# converter_adapter.net
KiCad netlist of a schematic drawn in EAGLE
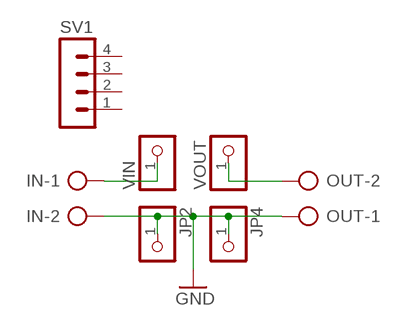
[diagram p0: schematic, sheet 1]

(export (version "E")
  (design (tool "Eeschema 10.0.6"))
  (components
    (comp (ref "IN")
      (value "AK500/2-H")
      (footprint "eagle-import:AK500_2-H")
      (libsource (lib "eagle-import") (part "AK500/2-H"))
    )
    (comp (ref "JP2")
      (value "PINHD-1X1")
      (footprint "eagle-import:1X01")
      (libsource (lib "eagle-import") (part "PINHD-1X1"))
    )
    (comp (ref "JP4")
      (value "PINHD-1X1")
      (footprint "eagle-import:1X01")
      (libsource (lib "eagle-import") (part "PINHD-1X1"))
    )
    (comp (ref "OUT")
      (value "AK500/2-H")
      (footprint "eagle-import:AK500_2-H")
      (libsource (lib "eagle-import") (part "AK500/2-H"))
    )
    (comp (ref "SV1")
      (value "MA04-1")
      (footprint "eagle-import:MA04-1")
      (libsource (lib "eagle-import") (part "MA04-1"))
    )
    (comp (ref "VIN")
      (value "PINHD-1X1")
      (footprint "eagle-import:1X01")
      (libsource (lib "eagle-import") (part "PINHD-1X1"))
    )
    (comp (ref "VOUT")
      (value "PINHD-1X1")
      (footprint "eagle-import:1X01")
      (libsource (lib "eagle-import") (part "PINHD-1X1"))
    )
  )
  (nets
    (net (code "1") (name "GND") (class "Default")
      (node (ref "IN") (pin "2") (pinfunction "KL_2") (pintype "passive"))
      (node (ref "JP2") (pin "1") (pinfunction "1_1") (pintype "passive"))
      (node (ref "JP4") (pin "1") (pinfunction "1_1") (pintype "passive"))
      (node (ref "OUT") (pin "1") (pinfunction "KL_1") (pintype "passive"))
    )
    (net (code "2") (name "Net-(INA-KL)") (class "Default")
      (node (ref "IN") (pin "1") (pinfunction "KL_1") (pintype "passive"))
      (node (ref "VIN") (pin "1") (pinfunction "1_1") (pintype "passive"))
    )
    (net (code "3") (name "Net-(OUTB-KL)") (class "Default")
      (node (ref "OUT") (pin "2") (pinfunction "KL_2") (pintype "passive"))
      (node (ref "VOUT") (pin "1") (pinfunction "1_1") (pintype "passive"))
    )
    (net (code "4") (name "unconnected-(SV1-Pad1)") (class "Default")
      (node (ref "SV1") (pin "1") (pinfunction "1_1") (pintype "passive"))
    )
    (net (code "5") (name "unconnected-(SV1-Pad2)") (class "Default")
      (node (ref "SV1") (pin "2") (pinfunction "2_2") (pintype "passive"))
    )
    (net (code "6") (name "unconnected-(SV1-Pad3)") (class "Default")
      (node (ref "SV1") (pin "3") (pinfunction "3_3") (pintype "passive"))
    )
    (net (code "7") (name "unconnected-(SV1-Pad4)") (class "Default")
      (node (ref "SV1") (pin "4") (pinfunction "4_4") (pintype "passive"))
    )
  )
)
